# meio.net
KiCad netlist of a schematic drawn in EAGLE
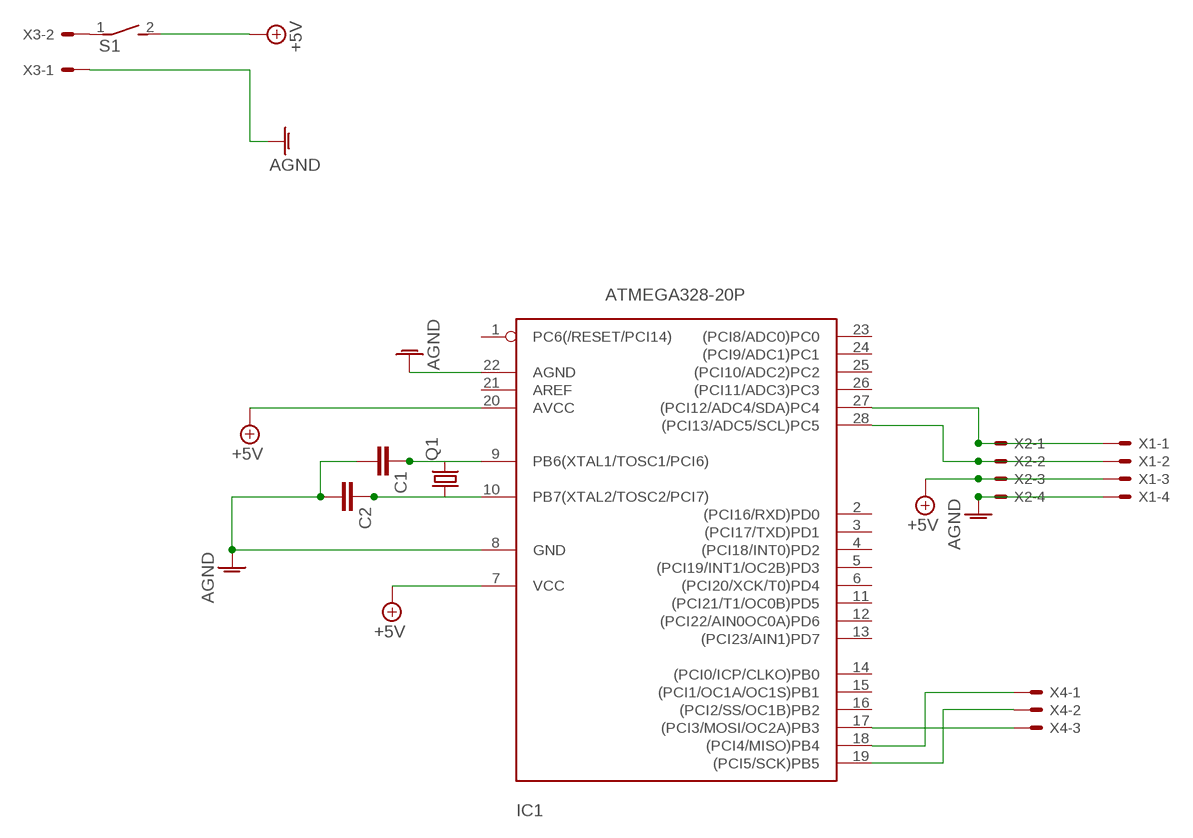
[diagram p0: schematic, sheet 1]

(export (version "E")
  (design (tool "Eeschema 10.0.6"))
  (components
    (comp (ref "C1")
      (value "C-EU025-025X050")
      (footprint "eagle-import:C025-025X050")
      (libsource (lib "eagle-import") (part "C-EU025-025X050"))
    )
    (comp (ref "C2")
      (value "C-EU025-025X050")
      (footprint "eagle-import:C025-025X050")
      (libsource (lib "eagle-import") (part "C-EU025-025X050"))
    )
    (comp (ref "IC1")
      (value "ATMEGA328-20P")
      (footprint "eagle-import:DIL28-3")
      (libsource (lib "eagle-import") (part "ATMEGA328P-20"))
    )
    (comp (ref "Q1")
      (value "CRYSTALHC49S")
      (footprint "eagle-import:HC49_S")
      (libsource (lib "eagle-import") (part "CRYSTALHC49S"))
    )
    (comp (ref "S1")
      (value "DS01E")
      (footprint "eagle-import:DS-01")
      (libsource (lib "eagle-import") (part "DS01E"))
    )
    (comp (ref "X1")
      (value "KK-156-4")
      (footprint "eagle-import:KK-156-4")
      (fields (field (name "MF") "MOLEX"))
      (libsource (lib "eagle-import") (part "KK-156-4"))
    )
    (comp (ref "X2")
      (value "KK-156-4")
      (footprint "eagle-import:KK-156-4")
      (fields (field (name "MF") "MOLEX"))
      (libsource (lib "eagle-import") (part "KK-156-4"))
    )
    (comp (ref "X3")
      (value "KK-156-2")
      (footprint "eagle-import:KK-156-2")
      (fields (field (name "MF") "MOLEX"))
      (libsource (lib "eagle-import") (part "KK-156-2"))
    )
    (comp (ref "X4")
      (value "KK-156-3")
      (footprint "eagle-import:KK-156-3")
      (fields (field (name "MF") "MOLEX"))
      (libsource (lib "eagle-import") (part "KK-156-3"))
    )
  )
  (nets
    (net (code "1") (name "+5V") (class "Default")
      (node (ref "IC1") (pin "20") (pinfunction "AVCC_20") (pintype "bidirectional"))
      (node (ref "IC1") (pin "7") (pinfunction "VCC_7") (pintype "bidirectional"))
      (node (ref "S1") (pin "2") (pinfunction "2_2") (pintype "passive"))
      (node (ref "X1") (pin "3") (pinfunction "S_3") (pintype "passive"))
      (node (ref "X2") (pin "3") (pinfunction "S_3") (pintype "passive"))
    )
    (net (code "2") (name "AGND") (class "Default")
      (node (ref "C1") (pin "2") (pinfunction "2_2") (pintype "passive"))
      (node (ref "C2") (pin "2") (pinfunction "2_2") (pintype "passive"))
      (node (ref "IC1") (pin "22") (pinfunction "AGND_22") (pintype "bidirectional"))
      (node (ref "IC1") (pin "8") (pinfunction "GND_8") (pintype "bidirectional"))
      (node (ref "X1") (pin "4") (pinfunction "S_4") (pintype "passive"))
      (node (ref "X2") (pin "4") (pinfunction "S_4") (pintype "passive"))
      (node (ref "X3") (pin "1") (pinfunction "S_1") (pintype "passive"))
    )
    (net (code "3") (name "Net-(IC1-(PCI3{slash}MOSI{slash}OC2A)PB3)") (class "Default")
      (node (ref "IC1") (pin "17") (pinfunction "(PCI3/MOSI/OC2A)PB3_17") (pintype "bidirectional"))
      (node (ref "X4") (pin "3") (pinfunction "S_3") (pintype "passive"))
    )
    (net (code "4") (name "Net-(IC1-(PCI4{slash}MISO)PB4)") (class "Default")
      (node (ref "IC1") (pin "18") (pinfunction "(PCI4/MISO)PB4_18") (pintype "bidirectional"))
      (node (ref "X4") (pin "1") (pinfunction "S_1") (pintype "passive"))
    )
    (net (code "5") (name "Net-(IC1-(PCI5{slash}SCK)PB5)") (class "Default")
      (node (ref "IC1") (pin "19") (pinfunction "(PCI5/SCK)PB5_19") (pintype "bidirectional"))
      (node (ref "X4") (pin "2") (pinfunction "S_2") (pintype "passive"))
    )
    (net (code "6") (name "Net-(IC1-(PCI12{slash}ADC4{slash}SDA)PC4)") (class "Default")
      (node (ref "IC1") (pin "27") (pinfunction "(PCI12/ADC4/SDA)PC4_27") (pintype "bidirectional"))
      (node (ref "X1") (pin "1") (pinfunction "S_1") (pintype "passive"))
      (node (ref "X2") (pin "1") (pinfunction "S_1") (pintype "passive"))
    )
    (net (code "7") (name "Net-(IC1-(PCI13{slash}ADC5{slash}SCL)PC5)") (class "Default")
      (node (ref "IC1") (pin "28") (pinfunction "(PCI13/ADC5/SCL)PC5_28") (pintype "bidirectional"))
      (node (ref "X1") (pin "2") (pinfunction "S_2") (pintype "passive"))
      (node (ref "X2") (pin "2") (pinfunction "S_2") (pintype "passive"))
    )
    (net (code "8") (name "Net-(IC1-PB6(XTAL1{slash}TOSC1{slash}PCI6))") (class "Default")
      (node (ref "C1") (pin "1") (pinfunction "1_1") (pintype "passive"))
      (node (ref "IC1") (pin "9") (pinfunction "PB6(XTAL1/TOSC1/PCI6)_9") (pintype "bidirectional"))
      (node (ref "Q1") (pin "2") (pinfunction "2_2") (pintype "passive"))
    )
    (net (code "9") (name "Net-(IC1-PB7(XTAL2{slash}TOSC2{slash}PCI7))") (class "Default")
      (node (ref "C2") (pin "1") (pinfunction "1_1") (pintype "passive"))
      (node (ref "IC1") (pin "10") (pinfunction "PB7(XTAL2/TOSC2/PCI7)_10") (pintype "bidirectional"))
      (node (ref "Q1") (pin "1") (pinfunction "1_1") (pintype "passive"))
    )
    (net (code "10") (name "Net-(X3B-S)") (class "Default")
      (node (ref "S1") (pin "1") (pinfunction "1_1") (pintype "passive"))
      (node (ref "X3") (pin "2") (pinfunction "S_2") (pintype "passive"))
    )
    (net (code "11") (name "unconnected-(IC1-(PCI0{slash}ICP{slash}CLKO)PB0-Pad14)") (class "Default")
      (node (ref "IC1") (pin "14") (pinfunction "(PCI0/ICP/CLKO)PB0_14") (pintype "bidirectional"))
    )
    (net (code "12") (name "unconnected-(IC1-(PCI1{slash}OC1A{slash}OC1S)PB1-Pad15)") (class "Default")
      (node (ref "IC1") (pin "15") (pinfunction "(PCI1/OC1A/OC1S)PB1_15") (pintype "bidirectional"))
    )
    (net (code "13") (name "unconnected-(IC1-(PCI2{slash}SS{slash}OC1B)PB2-Pad16)") (class "Default")
      (node (ref "IC1") (pin "16") (pinfunction "(PCI2/SS/OC1B)PB2_16") (pintype "bidirectional"))
    )
    (net (code "14") (name "unconnected-(IC1-(PCI8{slash}ADC0)PC0-Pad23)") (class "Default")
      (node (ref "IC1") (pin "23") (pinfunction "(PCI8/ADC0)PC0_23") (pintype "bidirectional"))
    )
    (net (code "15") (name "unconnected-(IC1-(PCI9{slash}ADC1)PC1-Pad24)") (class "Default")
      (node (ref "IC1") (pin "24") (pinfunction "(PCI9/ADC1)PC1_24") (pintype "bidirectional"))
    )
    (net (code "16") (name "unconnected-(IC1-(PCI10{slash}ADC2)PC2-Pad25)") (class "Default")
      (node (ref "IC1") (pin "25") (pinfunction "(PCI10/ADC2)PC2_25") (pintype "bidirectional"))
    )
    (net (code "17") (name "unconnected-(IC1-(PCI11{slash}ADC3)PC3-Pad26)") (class "Default")
      (node (ref "IC1") (pin "26") (pinfunction "(PCI11/ADC3)PC3_26") (pintype "bidirectional"))
    )
    (net (code "18") (name "unconnected-(IC1-(PCI16{slash}RXD)PD0-Pad2)") (class "Default")
      (node (ref "IC1") (pin "2") (pinfunction "(PCI16/RXD)PD0_2") (pintype "bidirectional"))
    )
    (net (code "19") (name "unconnected-(IC1-(PCI17{slash}TXD)PD1-Pad3)") (class "Default")
      (node (ref "IC1") (pin "3") (pinfunction "(PCI17/TXD)PD1_3") (pintype "bidirectional"))
    )
    (net (code "20") (name "unconnected-(IC1-(PCI18{slash}INT0)PD2-Pad4)") (class "Default")
      (node (ref "IC1") (pin "4") (pinfunction "(PCI18/INT0)PD2_4") (pintype "bidirectional"))
    )
    (net (code "21") (name "unconnected-(IC1-(PCI19{slash}INT1{slash}OC2B)PD3-Pad5)") (class "Default")
      (node (ref "IC1") (pin "5") (pinfunction "(PCI19/INT1/OC2B)PD3_5") (pintype "bidirectional"))
    )
    (net (code "22") (name "unconnected-(IC1-(PCI20{slash}XCK{slash}T0)PD4-Pad6)") (class "Default")
      (node (ref "IC1") (pin "6") (pinfunction "(PCI20/XCK/T0)PD4_6") (pintype "bidirectional"))
    )
    (net (code "23") (name "unconnected-(IC1-(PCI21{slash}T1{slash}OC0B)PD5-Pad11)") (class "Default")
      (node (ref "IC1") (pin "11") (pinfunction "(PCI21/T1/OC0B)PD5_11") (pintype "bidirectional"))
    )
    (net (code "24") (name "unconnected-(IC1-(PCI22{slash}AIN0OC0A)PD6-Pad12)") (class "Default")
      (node (ref "IC1") (pin "12") (pinfunction "(PCI22/AIN0OC0A)PD6_12") (pintype "bidirectional"))
    )
    (net (code "25") (name "unconnected-(IC1-(PCI23{slash}AIN1)PD7-Pad13)") (class "Default")
      (node (ref "IC1") (pin "13") (pinfunction "(PCI23/AIN1)PD7_13") (pintype "bidirectional"))
    )
    (net (code "26") (name "unconnected-(IC1-AREF-Pad21)") (class "Default")
      (node (ref "IC1") (pin "21") (pinfunction "AREF_21") (pintype "bidirectional"))
    )
    (net (code "27") (name "unconnected-(IC1-PC6({slash}RESET{slash}PCI14)-Pad1)") (class "Default")
      (node (ref "IC1") (pin "1") (pinfunction "PC6(/RESET/PCI14)_1") (pintype "bidirectional"))
    )
  )
)
